# Card_Edge_Board.net
KiCad netlist of a schematic drawn in EAGLE
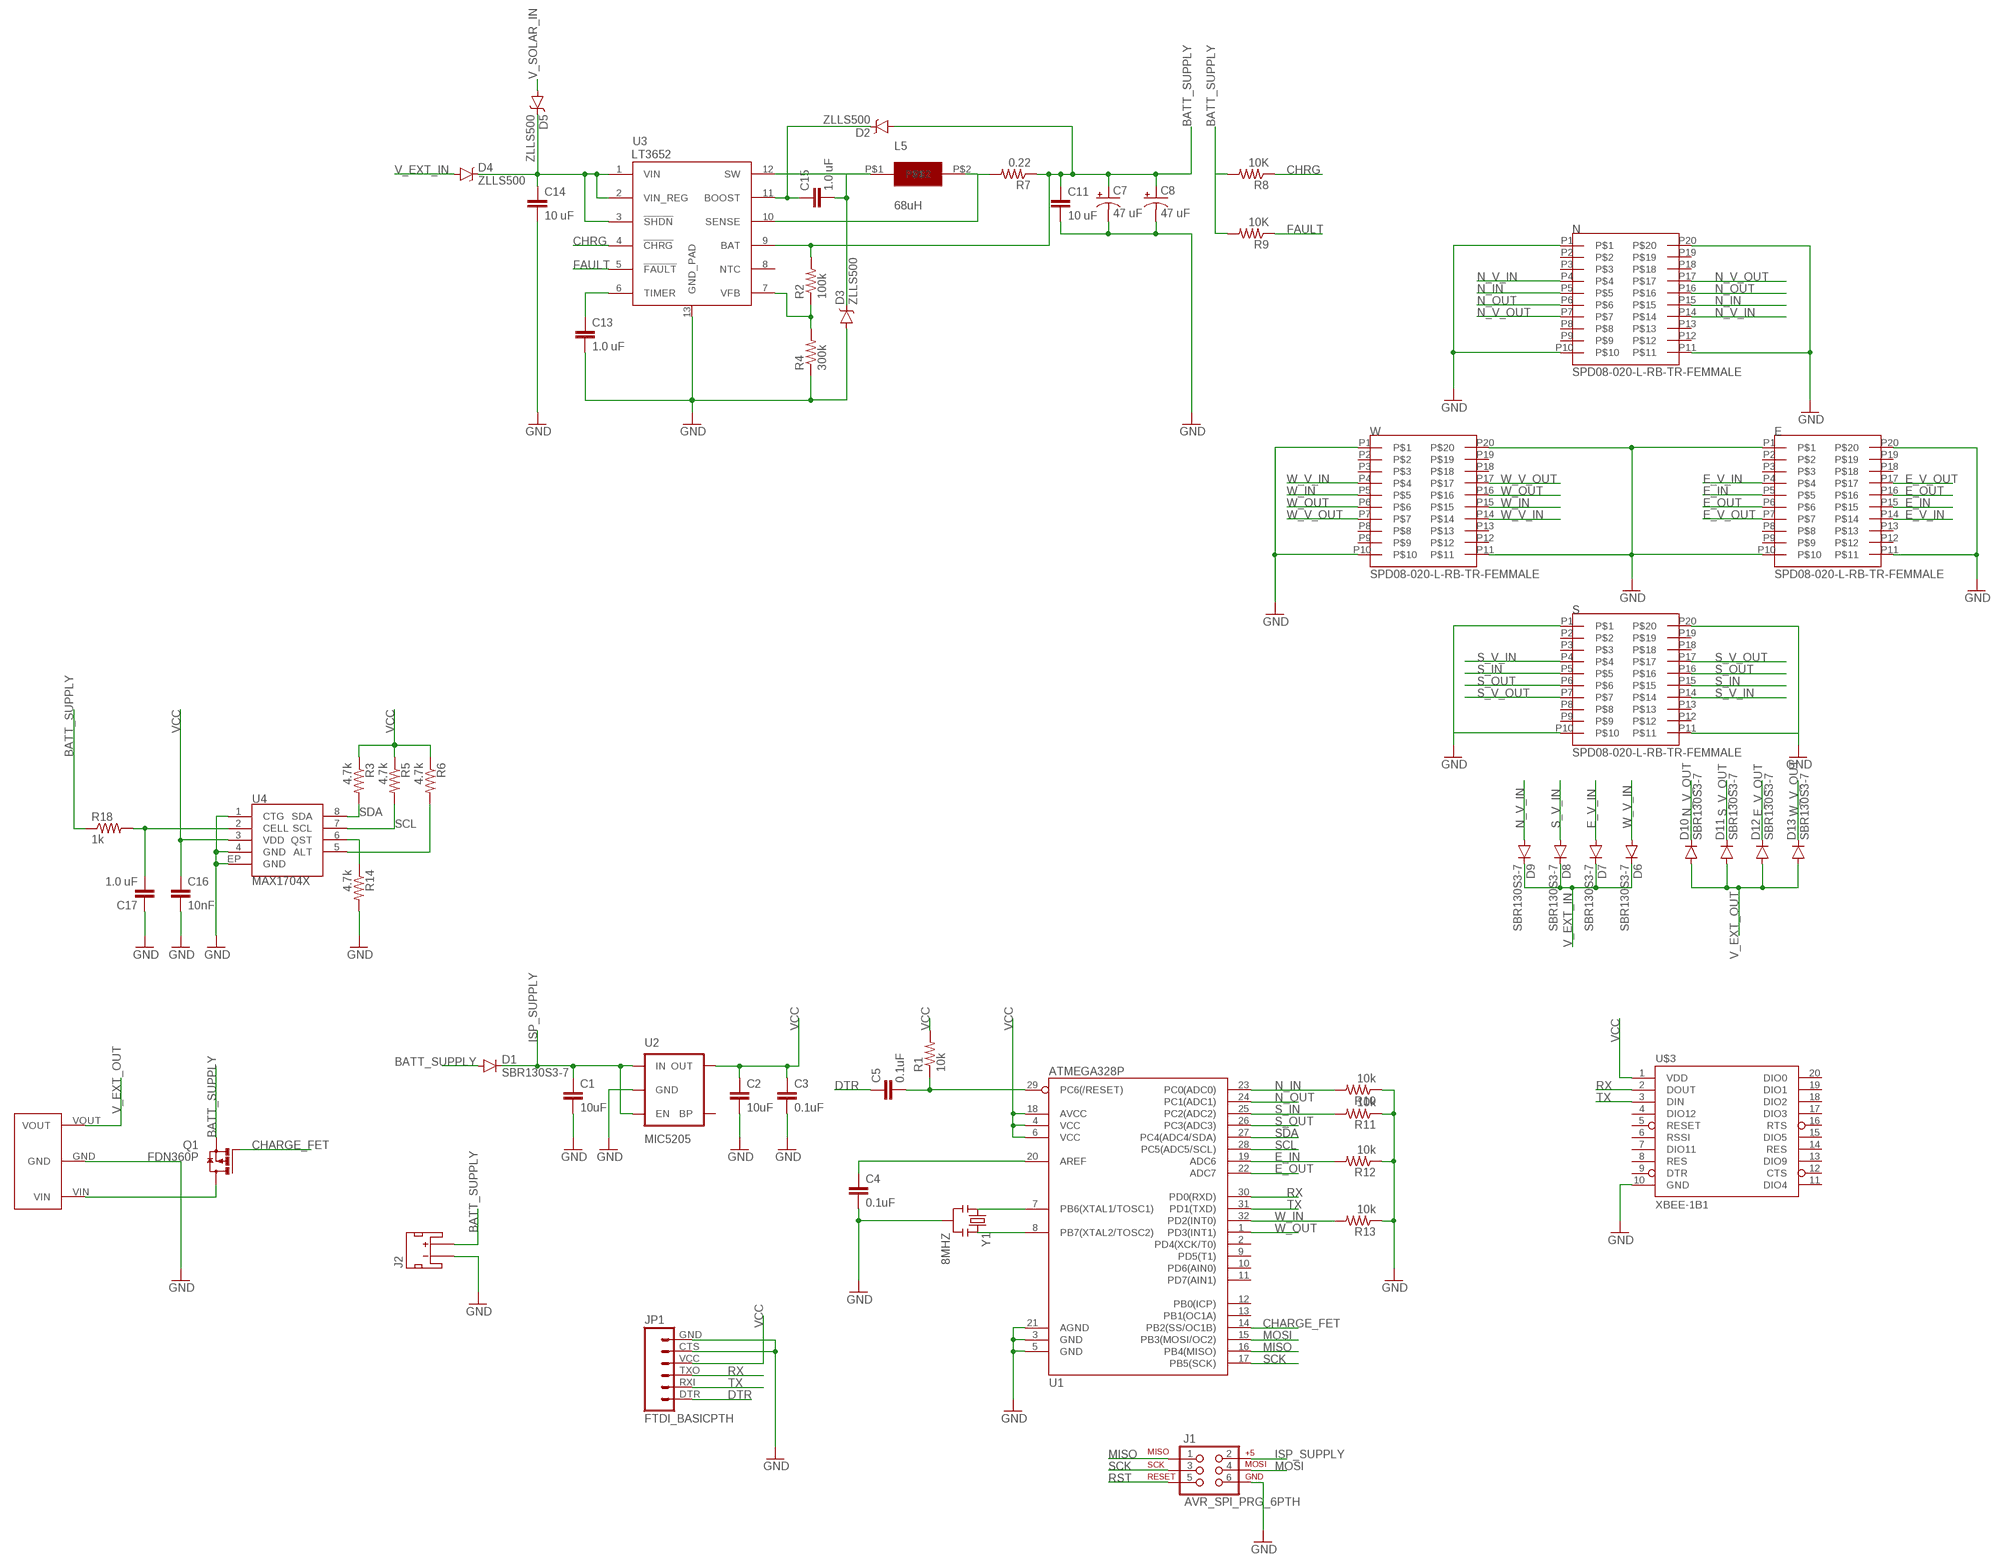
[diagram p0: schematic, sheet 1]

(export (version "E")
  (design (tool "Eeschema 10.0.6"))
  (components
    (comp (ref "C1")
      (value "10uF")
      (footprint "eagle-import:1206")
      (libsource (lib "eagle-import") (part "CAP1206"))
    )
    (comp (ref "C2")
      (value "10uF")
      (footprint "eagle-import:1206")
      (libsource (lib "eagle-import") (part "CAP1206"))
    )
    (comp (ref "C3")
      (value "0.1uF")
      (footprint "eagle-import:1206")
      (libsource (lib "eagle-import") (part "CAP1206"))
    )
    (comp (ref "C4")
      (value "0.1uF")
      (footprint "eagle-import:1206")
      (libsource (lib "eagle-import") (part "CAP1206"))
    )
    (comp (ref "C5")
      (value "0.1uF")
      (footprint "eagle-import:1206")
      (libsource (lib "eagle-import") (part "CAP1206"))
    )
    (comp (ref "C7")
      (value "47 uF")
      (footprint "eagle-import:EIA3216")
      (libsource (lib "eagle-import") (part "CAP_POL1206"))
    )
    (comp (ref "C8")
      (value "47 uF")
      (footprint "eagle-import:EIA3216")
      (libsource (lib "eagle-import") (part "CAP_POL1206"))
    )
    (comp (ref "C11")
      (value "10 uF")
      (footprint "eagle-import:1206")
      (libsource (lib "eagle-import") (part "10UF-6.3V-20%(1206)"))
    )
    (comp (ref "C13")
      (value "1.0 uF")
      (footprint "eagle-import:1206")
      (libsource (lib "eagle-import") (part "10UF-6.3V-20%(1206)"))
    )
    (comp (ref "C14")
      (value "10 uF")
      (footprint "eagle-import:1206")
      (libsource (lib "eagle-import") (part "10UF-6.3V-20%(1206)"))
    )
    (comp (ref "C15")
      (value "1.0 uF")
      (footprint "eagle-import:1206")
      (libsource (lib "eagle-import") (part "10UF-6.3V-20%(1206)"))
    )
    (comp (ref "C16")
      (value "10nF")
      (footprint "eagle-import:1206")
      (libsource (lib "eagle-import") (part "10UF-6.3V-20%(1206)"))
    )
    (comp (ref "C17")
      (value "1.0 uF")
      (footprint "eagle-import:1206")
      (libsource (lib "eagle-import") (part "10UF-6.3V-20%(1206)"))
    )
    (comp (ref "D1")
      (value "SBR130S3-7")
      (footprint "eagle-import:SOD-323")
      (libsource (lib "eagle-import") (part "DIODESOD"))
    )
    (comp (ref "D2")
      (value "ZLLS500")
      (footprint "eagle-import:SOT23")
      (libsource (lib "eagle-import") (part "ZLLS500ZLLS500"))
    )
    (comp (ref "D3")
      (value "ZLLS500")
      (footprint "eagle-import:SOT23")
      (libsource (lib "eagle-import") (part "ZLLS500ZLLS500"))
    )
    (comp (ref "D4")
      (value "ZLLS500")
      (footprint "eagle-import:SOT23")
      (libsource (lib "eagle-import") (part "ZLLS500ZLLS500"))
    )
    (comp (ref "D5")
      (value "ZLLS500")
      (footprint "eagle-import:SOT23")
      (libsource (lib "eagle-import") (part "ZLLS500ZLLS500"))
    )
    (comp (ref "D6")
      (value "SBR130S3-7")
      (footprint "eagle-import:SOD-323")
      (libsource (lib "eagle-import") (part "DIODESOD"))
    )
    (comp (ref "D7")
      (value "SBR130S3-7")
      (footprint "eagle-import:SOD-323")
      (libsource (lib "eagle-import") (part "DIODESOD"))
    )
    (comp (ref "D8")
      (value "SBR130S3-7")
      (footprint "eagle-import:SOD-323")
      (libsource (lib "eagle-import") (part "DIODESOD"))
    )
    (comp (ref "D9")
      (value "SBR130S3-7")
      (footprint "eagle-import:SOD-323")
      (libsource (lib "eagle-import") (part "DIODESOD"))
    )
    (comp (ref "D10")
      (value "SBR130S3-7")
      (footprint "eagle-import:SOD-323")
      (libsource (lib "eagle-import") (part "DIODESOD"))
    )
    (comp (ref "D11")
      (value "SBR130S3-7")
      (footprint "eagle-import:SOD-323")
      (libsource (lib "eagle-import") (part "DIODESOD"))
    )
    (comp (ref "D12")
      (value "SBR130S3-7")
      (footprint "eagle-import:SOD-323")
      (libsource (lib "eagle-import") (part "DIODESOD"))
    )
    (comp (ref "D13")
      (value "SBR130S3-7")
      (footprint "eagle-import:SOD-323")
      (libsource (lib "eagle-import") (part "DIODESOD"))
    )
    (comp (ref "E")
      (value "SPD08-020-L-RB-TR-FEMMALE")
      (footprint "eagle-import:SPD08-020-L-RB-TR-FOOT")
      (libsource (lib "eagle-import") (part "SPD08-020-L-RB-TR-FEMMALE"))
    )
    (comp (ref "J1")
      (value "AVR_SPI_PRG_6PTH")
      (footprint "eagle-import:2X3")
      (libsource (lib "eagle-import") (part "AVR_SPI_PRG_6PTH"))
    )
    (comp (ref "J2")
      (value "JST_2MM_MALE")
      (footprint "eagle-import:JST-2-SMD")
      (libsource (lib "eagle-import") (part "JST_2MM_MALE"))
    )
    (comp (ref "JP1")
      (value "FTDI_BASICPTH")
      (footprint "eagle-import:FTDI_BASIC")
      (libsource (lib "eagle-import") (part "FTDI_BASICPTH"))
    )
    (comp (ref "L5")
      (value "68uH")
      (footprint "eagle-import:MURATA_29L68C")
      (libsource (lib "eagle-import") (part "MURATA_29L683CSMD1"))
    )
    (comp (ref "N")
      (value "SPD08-020-L-RB-TR-FEMMALE")
      (footprint "eagle-import:SPD08-020-L-RB-TR-FOOT")
      (libsource (lib "eagle-import") (part "SPD08-020-L-RB-TR-FEMMALE"))
    )
    (comp (ref "Q1")
      (value "FDN360P")
      (footprint "eagle-import:SUPER-SOT3")
      (libsource (lib "eagle-import") (part "FDN360P"))
    )
    (comp (ref "R1")
      (value "10k")
      (footprint "eagle-import:1206")
      (libsource (lib "eagle-import") (part "RESISTOR1206"))
    )
    (comp (ref "R2")
      (value "100k")
      (footprint "eagle-import:1206")
      (libsource (lib "eagle-import") (part "RESISTOR1206"))
    )
    (comp (ref "R3")
      (value "4.7k")
      (footprint "eagle-import:1206")
      (libsource (lib "eagle-import") (part "RESISTOR1206"))
    )
    (comp (ref "R4")
      (value "300k")
      (footprint "eagle-import:1206")
      (libsource (lib "eagle-import") (part "RESISTOR1206"))
    )
    (comp (ref "R5")
      (value "4.7k")
      (footprint "eagle-import:1206")
      (libsource (lib "eagle-import") (part "RESISTOR1206"))
    )
    (comp (ref "R6")
      (value "4.7k")
      (footprint "eagle-import:1206")
      (libsource (lib "eagle-import") (part "RESISTOR1206"))
    )
    (comp (ref "R7")
      (value "0.22")
      (footprint "eagle-import:1206")
      (libsource (lib "eagle-import") (part "RESISTOR1206"))
    )
    (comp (ref "R8")
      (value "10K")
      (footprint "eagle-import:1206")
      (libsource (lib "eagle-import") (part "RESISTOR1206"))
    )
    (comp (ref "R9")
      (value "10K")
      (footprint "eagle-import:1206")
      (libsource (lib "eagle-import") (part "RESISTOR1206"))
    )
    (comp (ref "R10")
      (value "10k")
      (footprint "eagle-import:1206")
      (libsource (lib "eagle-import") (part "RESISTOR1206"))
    )
    (comp (ref "R11")
      (value "10k")
      (footprint "eagle-import:1206")
      (libsource (lib "eagle-import") (part "RESISTOR1206"))
    )
    (comp (ref "R12")
      (value "10k")
      (footprint "eagle-import:1206")
      (libsource (lib "eagle-import") (part "RESISTOR1206"))
    )
    (comp (ref "R13")
      (value "10k")
      (footprint "eagle-import:1206")
      (libsource (lib "eagle-import") (part "RESISTOR1206"))
    )
    (comp (ref "R14")
      (value "4.7k")
      (footprint "eagle-import:1206")
      (libsource (lib "eagle-import") (part "RESISTOR1206"))
    )
    (comp (ref "R18")
      (value "1k")
      (footprint "eagle-import:1206")
      (libsource (lib "eagle-import") (part "RESISTOR1206"))
    )
    (comp (ref "S")
      (value "SPD08-020-L-RB-TR-FEMMALE")
      (footprint "eagle-import:SPD08-020-L-RB-TR-FOOT")
      (libsource (lib "eagle-import") (part "SPD08-020-L-RB-TR-FEMMALE"))
    )
    (comp (ref "U$1")
      (value "POLOLU791BOOSTPOLOLU")
      (footprint "eagle-import:POLOLU791_BOOST")
      (libsource (lib "eagle-import") (part "POLOLU791BOOSTPOLOLU"))
    )
    (comp (ref "U$3")
      (value "XBEE-1B1")
      (footprint "eagle-import:XBEE-1")
      (libsource (lib "eagle-import") (part "XBEE-1B1"))
    )
    (comp (ref "U1")
      (value "ATMEGA328P")
      (footprint "eagle-import:TQFP32-08")
      (libsource (lib "eagle-import") (part "ATMEGA328_SMT"))
    )
    (comp (ref "U2")
      (value "MIC5205")
      (footprint "eagle-import:SOT23-5")
      (libsource (lib "eagle-import") (part "MIC52053.3V"))
    )
    (comp (ref "U3")
      (value "LT3652")
      (footprint "eagle-import:MSOP-12_GND")
      (libsource (lib "eagle-import") (part "LT3652"))
    )
    (comp (ref "U4")
      (value "MAX1704X")
      (footprint "eagle-import:TDFN-8")
      (libsource (lib "eagle-import") (part "MAX1704X"))
    )
    (comp (ref "W")
      (value "SPD08-020-L-RB-TR-FEMMALE")
      (footprint "eagle-import:SPD08-020-L-RB-TR-FOOT")
      (libsource (lib "eagle-import") (part "SPD08-020-L-RB-TR-FEMMALE"))
    )
    (comp (ref "Y1")
      (value "8MHZ")
      (footprint "eagle-import:RESONATOR-SMD")
      (libsource (lib "eagle-import") (part "RESONATOR8MHZ"))
    )
  )
  (nets
    (net (code "1") (name "/BATT_SUPPLY") (class "Default")
      (node (ref "C11") (pin "1") (pinfunction "1_1") (pintype "passive"))
      (node (ref "C7") (pin "A") (pinfunction "+_A") (pintype "passive"))
      (node (ref "C8") (pin "A") (pinfunction "+_A") (pintype "passive"))
      (node (ref "D1") (pin "A") (pinfunction "A_A") (pintype "passive"))
      (node (ref "D2") (pin "1") (pinfunction "A_1") (pintype "passive"))
      (node (ref "J2") (pin "2") (pinfunction "+_2") (pintype "bidirectional"))
      (node (ref "Q1") (pin "2") (pinfunction "S_2") (pintype "passive"))
      (node (ref "R18") (pin "1") (pinfunction "1_1") (pintype "passive"))
      (node (ref "R2") (pin "2") (pinfunction "2_2") (pintype "passive"))
      (node (ref "R7") (pin "1") (pinfunction "1_1") (pintype "passive"))
      (node (ref "R8") (pin "2") (pinfunction "2_2") (pintype "passive"))
      (node (ref "R9") (pin "2") (pinfunction "2_2") (pintype "passive"))
      (node (ref "U3") (pin "9") (pinfunction "BAT_9") (pintype "bidirectional"))
    )
    (net (code "2") (name "/CHARGE_FET") (class "Default")
      (node (ref "Q1") (pin "1") (pinfunction "G_1") (pintype "passive"))
      (node (ref "U1") (pin "14") (pinfunction "PB2(SS/OC1B)_14") (pintype "bidirectional"))
    )
    (net (code "3") (name "/CHRG") (class "Default")
      (node (ref "R8") (pin "1") (pinfunction "1_1") (pintype "passive"))
      (node (ref "U3") (pin "4") (pinfunction "~{CHRG}_4") (pintype "bidirectional"))
    )
    (net (code "4") (name "/DTR") (class "Default")
      (node (ref "C5") (pin "1") (pinfunction "1_1") (pintype "passive"))
      (node (ref "JP1") (pin "DTR") (pinfunction "1_DTR") (pintype "passive"))
    )
    (net (code "5") (name "/E_IN") (class "Default")
      (node (ref "E") (pin "P15") (pinfunction "P$15_P15") (pintype "bidirectional"))
      (node (ref "E") (pin "P5") (pinfunction "P$5_P5") (pintype "bidirectional"))
      (node (ref "R12") (pin "2") (pinfunction "2_2") (pintype "passive"))
      (node (ref "U1") (pin "19") (pinfunction "ADC6_19") (pintype "bidirectional"))
    )
    (net (code "6") (name "/E_OUT") (class "Default")
      (node (ref "E") (pin "P16") (pinfunction "P$16_P16") (pintype "bidirectional"))
      (node (ref "E") (pin "P6") (pinfunction "P$6_P6") (pintype "bidirectional"))
      (node (ref "U1") (pin "22") (pinfunction "ADC7_22") (pintype "bidirectional"))
    )
    (net (code "7") (name "/E_V_IN") (class "Default")
      (node (ref "D7") (pin "A") (pinfunction "A_A") (pintype "passive"))
      (node (ref "E") (pin "P14") (pinfunction "P$14_P14") (pintype "bidirectional"))
      (node (ref "E") (pin "P4") (pinfunction "P$4_P4") (pintype "bidirectional"))
    )
    (net (code "8") (name "/E_V_OUT") (class "Default")
      (node (ref "D12") (pin "C") (pinfunction "C_C") (pintype "passive"))
      (node (ref "E") (pin "P17") (pinfunction "P$17_P17") (pintype "bidirectional"))
      (node (ref "E") (pin "P7") (pinfunction "P$7_P7") (pintype "bidirectional"))
    )
    (net (code "9") (name "/FAULT") (class "Default")
      (node (ref "R9") (pin "1") (pinfunction "1_1") (pintype "passive"))
      (node (ref "U3") (pin "5") (pinfunction "~{FAULT}_5") (pintype "bidirectional"))
    )
    (net (code "10") (name "/ISP_SUPPLY") (class "Default")
      (node (ref "C1") (pin "1") (pinfunction "1_1") (pintype "passive"))
      (node (ref "D1") (pin "C") (pinfunction "C_C") (pintype "passive"))
      (node (ref "J1") (pin "2") (pinfunction "2_2") (pintype "passive"))
      (node (ref "U2") (pin "1") (pinfunction "IN_1") (pintype "input"))
      (node (ref "U2") (pin "3") (pinfunction "EN_3") (pintype "input"))
    )
    (net (code "11") (name "/MISO") (class "Default")
      (node (ref "J1") (pin "1") (pinfunction "1_1") (pintype "passive"))
      (node (ref "U1") (pin "16") (pinfunction "PB4(MISO)_16") (pintype "bidirectional"))
    )
    (net (code "12") (name "/MOSI") (class "Default")
      (node (ref "J1") (pin "4") (pinfunction "4_4") (pintype "passive"))
      (node (ref "U1") (pin "15") (pinfunction "PB3(MOSI/OC2)_15") (pintype "bidirectional"))
    )
    (net (code "13") (name "/N_IN") (class "Default")
      (node (ref "N") (pin "P15") (pinfunction "P$15_P15") (pintype "bidirectional"))
      (node (ref "N") (pin "P5") (pinfunction "P$5_P5") (pintype "bidirectional"))
      (node (ref "R10") (pin "2") (pinfunction "2_2") (pintype "passive"))
      (node (ref "U1") (pin "23") (pinfunction "PC0(ADC0)_23") (pintype "bidirectional"))
    )
    (net (code "14") (name "/N_OUT") (class "Default")
      (node (ref "N") (pin "P16") (pinfunction "P$16_P16") (pintype "bidirectional"))
      (node (ref "N") (pin "P6") (pinfunction "P$6_P6") (pintype "bidirectional"))
      (node (ref "U1") (pin "24") (pinfunction "PC1(ADC1)_24") (pintype "bidirectional"))
    )
    (net (code "15") (name "/N_V_IN") (class "Default")
      (node (ref "D9") (pin "A") (pinfunction "A_A") (pintype "passive"))
      (node (ref "N") (pin "P14") (pinfunction "P$14_P14") (pintype "bidirectional"))
      (node (ref "N") (pin "P4") (pinfunction "P$4_P4") (pintype "bidirectional"))
    )
    (net (code "16") (name "/N_V_OUT") (class "Default")
      (node (ref "D10") (pin "C") (pinfunction "C_C") (pintype "passive"))
      (node (ref "N") (pin "P17") (pinfunction "P$17_P17") (pintype "bidirectional"))
      (node (ref "N") (pin "P7") (pinfunction "P$7_P7") (pintype "bidirectional"))
    )
    (net (code "17") (name "/RST") (class "Default")
      (node (ref "C5") (pin "2") (pinfunction "2_2") (pintype "passive"))
      (node (ref "J1") (pin "5") (pinfunction "5_5") (pintype "passive"))
      (node (ref "R1") (pin "1") (pinfunction "1_1") (pintype "passive"))
      (node (ref "U1") (pin "29") (pinfunction "PC6(/RESET)_29") (pintype "bidirectional"))
    )
    (net (code "18") (name "/RX") (class "Default")
      (node (ref "JP1") (pin "TXO") (pinfunction "3_TXO") (pintype "passive"))
      (node (ref "U$3") (pin "2") (pinfunction "DOUT_2") (pintype "output"))
      (node (ref "U1") (pin "30") (pinfunction "PD0(RXD)_30") (pintype "bidirectional"))
    )
    (net (code "19") (name "/SCK") (class "Default")
      (node (ref "J1") (pin "3") (pinfunction "3_3") (pintype "passive"))
      (node (ref "U1") (pin "17") (pinfunction "PB5(SCK)_17") (pintype "bidirectional"))
    )
    (net (code "20") (name "/SCL") (class "Default")
      (node (ref "R5") (pin "2") (pinfunction "2_2") (pintype "passive"))
      (node (ref "U1") (pin "28") (pinfunction "PC5(ADC5/SCL)_28") (pintype "bidirectional"))
      (node (ref "U4") (pin "7") (pinfunction "SCL_7") (pintype "bidirectional"))
    )
    (net (code "21") (name "/SDA") (class "Default")
      (node (ref "R3") (pin "2") (pinfunction "2_2") (pintype "passive"))
      (node (ref "U1") (pin "27") (pinfunction "PC4(ADC4/SDA)_27") (pintype "bidirectional"))
      (node (ref "U4") (pin "8") (pinfunction "SDA_8") (pintype "bidirectional"))
    )
    (net (code "22") (name "/S_IN") (class "Default")
      (node (ref "R11") (pin "2") (pinfunction "2_2") (pintype "passive"))
      (node (ref "S") (pin "P15") (pinfunction "P$15_P15") (pintype "bidirectional"))
      (node (ref "S") (pin "P5") (pinfunction "P$5_P5") (pintype "bidirectional"))
      (node (ref "U1") (pin "25") (pinfunction "PC2(ADC2)_25") (pintype "bidirectional"))
    )
    (net (code "23") (name "/S_OUT") (class "Default")
      (node (ref "S") (pin "P16") (pinfunction "P$16_P16") (pintype "bidirectional"))
      (node (ref "S") (pin "P6") (pinfunction "P$6_P6") (pintype "bidirectional"))
      (node (ref "U1") (pin "26") (pinfunction "PC3(ADC3)_26") (pintype "bidirectional"))
    )
    (net (code "24") (name "/S_V_IN") (class "Default")
      (node (ref "D8") (pin "A") (pinfunction "A_A") (pintype "passive"))
      (node (ref "S") (pin "P14") (pinfunction "P$14_P14") (pintype "bidirectional"))
      (node (ref "S") (pin "P4") (pinfunction "P$4_P4") (pintype "bidirectional"))
    )
    (net (code "25") (name "/S_V_OUT") (class "Default")
      (node (ref "D11") (pin "C") (pinfunction "C_C") (pintype "passive"))
      (node (ref "S") (pin "P17") (pinfunction "P$17_P17") (pintype "bidirectional"))
      (node (ref "S") (pin "P7") (pinfunction "P$7_P7") (pintype "bidirectional"))
    )
    (net (code "26") (name "/TX") (class "Default")
      (node (ref "JP1") (pin "RXI") (pinfunction "2_RXI") (pintype "passive"))
      (node (ref "U$3") (pin "3") (pinfunction "DIN_3") (pintype "input"))
      (node (ref "U1") (pin "31") (pinfunction "PD1(TXD)_31") (pintype "bidirectional"))
    )
    (net (code "27") (name "/VCC") (class "Default")
      (node (ref "C16") (pin "1") (pinfunction "1_1") (pintype "passive"))
      (node (ref "C2") (pin "1") (pinfunction "1_1") (pintype "passive"))
      (node (ref "C3") (pin "1") (pinfunction "1_1") (pintype "passive"))
      (node (ref "JP1") (pin "VCC") (pinfunction "4_VCC") (pintype "passive"))
      (node (ref "R1") (pin "2") (pinfunction "2_2") (pintype "passive"))
      (node (ref "R3") (pin "1") (pinfunction "1_1") (pintype "passive"))
      (node (ref "R5") (pin "1") (pinfunction "1_1") (pintype "passive"))
      (node (ref "R6") (pin "1") (pinfunction "1_1") (pintype "passive"))
      (node (ref "U$3") (pin "1") (pinfunction "VDD_1") (pintype "power_in"))
      (node (ref "U1") (pin "18") (pinfunction "AVCC_18") (pintype "bidirectional"))
      (node (ref "U1") (pin "4") (pinfunction "VCC_4") (pintype "bidirectional"))
      (node (ref "U1") (pin "6") (pinfunction "VCC_6") (pintype "bidirectional"))
      (node (ref "U2") (pin "5") (pinfunction "OUT_5") (pintype "passive"))
      (node (ref "U4") (pin "3") (pinfunction "VDD_3") (pintype "bidirectional"))
    )
    (net (code "28") (name "/V_EXT_IN") (class "Default")
      (node (ref "D4") (pin "1") (pinfunction "A_1") (pintype "passive"))
      (node (ref "D6") (pin "C") (pinfunction "C_C") (pintype "passive"))
      (node (ref "D7") (pin "C") (pinfunction "C_C") (pintype "passive"))
      (node (ref "D8") (pin "C") (pinfunction "C_C") (pintype "passive"))
      (node (ref "D9") (pin "C") (pinfunction "C_C") (pintype "passive"))
    )
    (net (code "29") (name "/V_EXT_OUT") (class "Default")
      (node (ref "D10") (pin "A") (pinfunction "A_A") (pintype "passive"))
      (node (ref "D11") (pin "A") (pinfunction "A_A") (pintype "passive"))
      (node (ref "D12") (pin "A") (pinfunction "A_A") (pintype "passive"))
      (node (ref "D13") (pin "A") (pinfunction "A_A") (pintype "passive"))
      (node (ref "U$1") (pin "VOUT") (pinfunction "VOUT_VOUT") (pintype "bidirectional"))
    )
    (net (code "30") (name "/V_SOLAR_IN") (class "Default")
      (node (ref "D5") (pin "1") (pinfunction "A_1") (pintype "passive"))
    )
    (net (code "31") (name "/W_IN") (class "Default")
      (node (ref "R13") (pin "2") (pinfunction "2_2") (pintype "passive"))
      (node (ref "U1") (pin "32") (pinfunction "PD2(INT0)_32") (pintype "bidirectional"))
      (node (ref "W") (pin "P15") (pinfunction "P$15_P15") (pintype "bidirectional"))
      (node (ref "W") (pin "P5") (pinfunction "P$5_P5") (pintype "bidirectional"))
    )
    (net (code "32") (name "/W_OUT") (class "Default")
      (node (ref "U1") (pin "1") (pinfunction "PD3(INT1)_1") (pintype "bidirectional"))
      (node (ref "W") (pin "P16") (pinfunction "P$16_P16") (pintype "bidirectional"))
      (node (ref "W") (pin "P6") (pinfunction "P$6_P6") (pintype "bidirectional"))
    )
    (net (code "33") (name "/W_V_IN") (class "Default")
      (node (ref "D6") (pin "A") (pinfunction "A_A") (pintype "passive"))
      (node (ref "W") (pin "P14") (pinfunction "P$14_P14") (pintype "bidirectional"))
      (node (ref "W") (pin "P4") (pinfunction "P$4_P4") (pintype "bidirectional"))
    )
    (net (code "34") (name "/W_V_OUT") (class "Default")
      (node (ref "D13") (pin "C") (pinfunction "C_C") (pintype "passive"))
      (node (ref "W") (pin "P17") (pinfunction "P$17_P17") (pintype "bidirectional"))
      (node (ref "W") (pin "P7") (pinfunction "P$7_P7") (pintype "bidirectional"))
    )
    (net (code "35") (name "GND") (class "Default")
      (node (ref "C1") (pin "2") (pinfunction "2_2") (pintype "passive"))
      (node (ref "C11") (pin "2") (pinfunction "2_2") (pintype "passive"))
      (node (ref "C13") (pin "2") (pinfunction "2_2") (pintype "passive"))
      (node (ref "C14") (pin "2") (pinfunction "2_2") (pintype "passive"))
      (node (ref "C16") (pin "2") (pinfunction "2_2") (pintype "passive"))
      (node (ref "C17") (pin "1") (pinfunction "1_1") (pintype "passive"))
      (node (ref "C2") (pin "2") (pinfunction "2_2") (pintype "passive"))
      (node (ref "C3") (pin "2") (pinfunction "2_2") (pintype "passive"))
      (node (ref "C4") (pin "2") (pinfunction "2_2") (pintype "passive"))
      (node (ref "C7") (pin "C") (pinfunction "-_C") (pintype "passive"))
      (node (ref "C8") (pin "C") (pinfunction "-_C") (pintype "passive"))
      (node (ref "D3") (pin "1") (pinfunction "A_1") (pintype "passive"))
      (node (ref "E") (pin "P1") (pinfunction "P$1_P1") (pintype "bidirectional"))
      (node (ref "E") (pin "P10") (pinfunction "P$10_P10") (pintype "bidirectional"))
      (node (ref "E") (pin "P11") (pinfunction "P$11_P11") (pintype "bidirectional"))
      (node (ref "E") (pin "P20") (pinfunction "P$20_P20") (pintype "bidirectional"))
      (node (ref "J1") (pin "6") (pinfunction "6_6") (pintype "passive"))
      (node (ref "J2") (pin "1") (pinfunction "-_1") (pintype "bidirectional"))
      (node (ref "JP1") (pin "CTS") (pinfunction "5_CTS") (pintype "passive"))
      (node (ref "JP1") (pin "GND") (pinfunction "6_GND") (pintype "passive"))
      (node (ref "N") (pin "P1") (pinfunction "P$1_P1") (pintype "bidirectional"))
      (node (ref "N") (pin "P10") (pinfunction "P$10_P10") (pintype "bidirectional"))
      (node (ref "N") (pin "P11") (pinfunction "P$11_P11") (pintype "bidirectional"))
      (node (ref "N") (pin "P20") (pinfunction "P$20_P20") (pintype "bidirectional"))
      (node (ref "R10") (pin "1") (pinfunction "1_1") (pintype "passive"))
      (node (ref "R11") (pin "1") (pinfunction "1_1") (pintype "passive"))
      (node (ref "R12") (pin "1") (pinfunction "1_1") (pintype "passive"))
      (node (ref "R13") (pin "1") (pinfunction "1_1") (pintype "passive"))
      (node (ref "R14") (pin "2") (pinfunction "2_2") (pintype "passive"))
      (node (ref "R4") (pin "1") (pinfunction "1_1") (pintype "passive"))
      (node (ref "S") (pin "P1") (pinfunction "P$1_P1") (pintype "bidirectional"))
      (node (ref "S") (pin "P10") (pinfunction "P$10_P10") (pintype "bidirectional"))
      (node (ref "S") (pin "P11") (pinfunction "P$11_P11") (pintype "bidirectional"))
      (node (ref "S") (pin "P20") (pinfunction "P$20_P20") (pintype "bidirectional"))
      (node (ref "U$1") (pin "GND") (pinfunction "GND_GND") (pintype "bidirectional"))
      (node (ref "U$3") (pin "10") (pinfunction "GND_10") (pintype "power_in"))
      (node (ref "U1") (pin "21") (pinfunction "AGND_21") (pintype "bidirectional"))
      (node (ref "U1") (pin "3") (pinfunction "GND_3") (pintype "bidirectional"))
      (node (ref "U1") (pin "5") (pinfunction "GND_5") (pintype "bidirectional"))
      (node (ref "U2") (pin "2") (pinfunction "GND_2") (pintype "input"))
      (node (ref "U3") (pin "13") (pinfunction "GND_PAD_13") (pintype "bidirectional"))
      (node (ref "U4") (pin "1") (pinfunction "CTG_1") (pintype "bidirectional"))
      (node (ref "U4") (pin "4") (pinfunction "GND_4") (pintype "bidirectional"))
      (node (ref "U4") (pin "EP") (pinfunction "GND_EP") (pintype "bidirectional"))
      (node (ref "W") (pin "P1") (pinfunction "P$1_P1") (pintype "bidirectional"))
      (node (ref "W") (pin "P10") (pinfunction "P$10_P10") (pintype "bidirectional"))
      (node (ref "W") (pin "P11") (pinfunction "P$11_P11") (pintype "bidirectional"))
      (node (ref "W") (pin "P20") (pinfunction "P$20_P20") (pintype "bidirectional"))
      (node (ref "Y1") (pin "2") (pinfunction "2_2") (pintype "passive"))
    )
    (net (code "36") (name "Net-(D2-C)") (class "Default")
      (node (ref "C15") (pin "1") (pinfunction "1_1") (pintype "passive"))
      (node (ref "D2") (pin "3") (pinfunction "C_3") (pintype "passive"))
      (node (ref "U3") (pin "11") (pinfunction "BOOST_11") (pintype "bidirectional"))
    )
    (net (code "37") (name "Net-(D3-C)") (class "Default")
      (node (ref "C15") (pin "2") (pinfunction "2_2") (pintype "passive"))
      (node (ref "D3") (pin "3") (pinfunction "C_3") (pintype "passive"))
      (node (ref "L5") (pin "P$1") (pinfunction "P$1_P$1") (pintype "bidirectional"))
      (node (ref "U3") (pin "12") (pinfunction "SW_12") (pintype "bidirectional"))
    )
    (net (code "38") (name "Net-(D4-C)") (class "Default")
      (node (ref "C14") (pin "1") (pinfunction "1_1") (pintype "passive"))
      (node (ref "D4") (pin "3") (pinfunction "C_3") (pintype "passive"))
      (node (ref "D5") (pin "3") (pinfunction "C_3") (pintype "passive"))
      (node (ref "U3") (pin "1") (pinfunction "VIN_1") (pintype "bidirectional"))
      (node (ref "U3") (pin "2") (pinfunction "VIN_REG_2") (pintype "bidirectional"))
      (node (ref "U3") (pin "3") (pinfunction "~{SHDN}_3") (pintype "bidirectional"))
    )
    (net (code "39") (name "Net-(Q1-D)") (class "Default")
      (node (ref "Q1") (pin "3") (pinfunction "D_3") (pintype "passive"))
      (node (ref "U$1") (pin "VIN") (pinfunction "VIN_VIN") (pintype "bidirectional"))
    )
    (net (code "40") (name "Net-(U1-AREF)") (class "Default")
      (node (ref "C4") (pin "1") (pinfunction "1_1") (pintype "passive"))
      (node (ref "U1") (pin "20") (pinfunction "AREF_20") (pintype "bidirectional"))
    )
    (net (code "41") (name "Net-(U1-PB6(XTAL1{slash}TOSC1))") (class "Default")
      (node (ref "U1") (pin "7") (pinfunction "PB6(XTAL1/TOSC1)_7") (pintype "bidirectional"))
      (node (ref "Y1") (pin "1") (pinfunction "1_1") (pintype "passive"))
    )
    (net (code "42") (name "Net-(U1-PB7(XTAL2{slash}TOSC2))") (class "Default")
      (node (ref "U1") (pin "8") (pinfunction "PB7(XTAL2/TOSC2)_8") (pintype "bidirectional"))
      (node (ref "Y1") (pin "3") (pinfunction "3_3") (pintype "passive"))
    )
    (net (code "43") (name "Net-(U3-SENSE)") (class "Default")
      (node (ref "L5") (pin "P$2") (pinfunction "P$2_P$2") (pintype "bidirectional"))
      (node (ref "R7") (pin "2") (pinfunction "2_2") (pintype "passive"))
      (node (ref "U3") (pin "10") (pinfunction "SENSE_10") (pintype "bidirectional"))
    )
    (net (code "44") (name "Net-(U3-TIMER)") (class "Default")
      (node (ref "C13") (pin "1") (pinfunction "1_1") (pintype "passive"))
      (node (ref "U3") (pin "6") (pinfunction "TIMER_6") (pintype "bidirectional"))
    )
    (net (code "45") (name "Net-(U3-VFB)") (class "Default")
      (node (ref "R2") (pin "1") (pinfunction "1_1") (pintype "passive"))
      (node (ref "R4") (pin "2") (pinfunction "2_2") (pintype "passive"))
      (node (ref "U3") (pin "7") (pinfunction "VFB_7") (pintype "bidirectional"))
    )
    (net (code "46") (name "Net-(U4-ALT)") (class "Default")
      (node (ref "R6") (pin "2") (pinfunction "2_2") (pintype "passive"))
      (node (ref "U4") (pin "5") (pinfunction "ALT_5") (pintype "bidirectional"))
    )
    (net (code "47") (name "Net-(U4-CELL)") (class "Default")
      (node (ref "C17") (pin "2") (pinfunction "2_2") (pintype "passive"))
      (node (ref "R18") (pin "2") (pinfunction "2_2") (pintype "passive"))
      (node (ref "U4") (pin "2") (pinfunction "CELL_2") (pintype "bidirectional"))
    )
    (net (code "48") (name "Net-(U4-QST)") (class "Default")
      (node (ref "R14") (pin "1") (pinfunction "1_1") (pintype "passive"))
      (node (ref "U4") (pin "6") (pinfunction "QST_6") (pintype "bidirectional"))
    )
    (net (code "49") (name "unconnected-(E-P$2-PadP2)") (class "Default")
      (node (ref "E") (pin "P2") (pinfunction "P$2_P2") (pintype "bidirectional"))
    )
    (net (code "50") (name "unconnected-(E-P$3-PadP3)") (class "Default")
      (node (ref "E") (pin "P3") (pinfunction "P$3_P3") (pintype "bidirectional"))
    )
    (net (code "51") (name "unconnected-(E-P$8-PadP8)") (class "Default")
      (node (ref "E") (pin "P8") (pinfunction "P$8_P8") (pintype "bidirectional"))
    )
    (net (code "52") (name "unconnected-(E-P$9-PadP9)") (class "Default")
      (node (ref "E") (pin "P9") (pinfunction "P$9_P9") (pintype "bidirectional"))
    )
    (net (code "53") (name "unconnected-(E-P$12-PadP12)") (class "Default")
      (node (ref "E") (pin "P12") (pinfunction "P$12_P12") (pintype "bidirectional"))
    )
    (net (code "54") (name "unconnected-(E-P$13-PadP13)") (class "Default")
      (node (ref "E") (pin "P13") (pinfunction "P$13_P13") (pintype "bidirectional"))
    )
    (net (code "55") (name "unconnected-(E-P$18-PadP18)") (class "Default")
      (node (ref "E") (pin "P18") (pinfunction "P$18_P18") (pintype "bidirectional"))
    )
    (net (code "56") (name "unconnected-(E-P$19-PadP19)") (class "Default")
      (node (ref "E") (pin "P19") (pinfunction "P$19_P19") (pintype "bidirectional"))
    )
    (net (code "57") (name "unconnected-(J2-PAD1-PadNC1)") (class "Default")
      (node (ref "J2") (pin "NC1") (pinfunction "PAD1_NC1") (pintype "bidirectional"))
    )
    (net (code "58") (name "unconnected-(J2-PAD2-PadNC2)") (class "Default")
      (node (ref "J2") (pin "NC2") (pinfunction "PAD2_NC2") (pintype "bidirectional"))
    )
    (net (code "59") (name "unconnected-(N-P$2-PadP2)") (class "Default")
      (node (ref "N") (pin "P2") (pinfunction "P$2_P2") (pintype "bidirectional"))
    )
    (net (code "60") (name "unconnected-(N-P$3-PadP3)") (class "Default")
      (node (ref "N") (pin "P3") (pinfunction "P$3_P3") (pintype "bidirectional"))
    )
    (net (code "61") (name "unconnected-(N-P$8-PadP8)") (class "Default")
      (node (ref "N") (pin "P8") (pinfunction "P$8_P8") (pintype "bidirectional"))
    )
    (net (code "62") (name "unconnected-(N-P$9-PadP9)") (class "Default")
      (node (ref "N") (pin "P9") (pinfunction "P$9_P9") (pintype "bidirectional"))
    )
    (net (code "63") (name "unconnected-(N-P$12-PadP12)") (class "Default")
      (node (ref "N") (pin "P12") (pinfunction "P$12_P12") (pintype "bidirectional"))
    )
    (net (code "64") (name "unconnected-(N-P$13-PadP13)") (class "Default")
      (node (ref "N") (pin "P13") (pinfunction "P$13_P13") (pintype "bidirectional"))
    )
    (net (code "65") (name "unconnected-(N-P$18-PadP18)") (class "Default")
      (node (ref "N") (pin "P18") (pinfunction "P$18_P18") (pintype "bidirectional"))
    )
    (net (code "66") (name "unconnected-(N-P$19-PadP19)") (class "Default")
      (node (ref "N") (pin "P19") (pinfunction "P$19_P19") (pintype "bidirectional"))
    )
    (net (code "67") (name "unconnected-(S-P$2-PadP2)") (class "Default")
      (node (ref "S") (pin "P2") (pinfunction "P$2_P2") (pintype "bidirectional"))
    )
    (net (code "68") (name "unconnected-(S-P$3-PadP3)") (class "Default")
      (node (ref "S") (pin "P3") (pinfunction "P$3_P3") (pintype "bidirectional"))
    )
    (net (code "69") (name "unconnected-(S-P$8-PadP8)") (class "Default")
      (node (ref "S") (pin "P8") (pinfunction "P$8_P8") (pintype "bidirectional"))
    )
    (net (code "70") (name "unconnected-(S-P$9-PadP9)") (class "Default")
      (node (ref "S") (pin "P9") (pinfunction "P$9_P9") (pintype "bidirectional"))
    )
    (net (code "71") (name "unconnected-(S-P$12-PadP12)") (class "Default")
      (node (ref "S") (pin "P12") (pinfunction "P$12_P12") (pintype "bidirectional"))
    )
    (net (code "72") (name "unconnected-(S-P$13-PadP13)") (class "Default")
      (node (ref "S") (pin "P13") (pinfunction "P$13_P13") (pintype "bidirectional"))
    )
    (net (code "73") (name "unconnected-(S-P$18-PadP18)") (class "Default")
      (node (ref "S") (pin "P18") (pinfunction "P$18_P18") (pintype "bidirectional"))
    )
    (net (code "74") (name "unconnected-(S-P$19-PadP19)") (class "Default")
      (node (ref "S") (pin "P19") (pinfunction "P$19_P19") (pintype "bidirectional"))
    )
    (net (code "75") (name "unconnected-(U$3-CTS-Pad12)") (class "Default")
      (node (ref "U$3") (pin "12") (pinfunction "CTS_12") (pintype "output"))
    )
    (net (code "76") (name "unconnected-(U$3-DIO0-Pad20)") (class "Default")
      (node (ref "U$3") (pin "20") (pinfunction "DIO0_20") (pintype "bidirectional"))
    )
    (net (code "77") (name "unconnected-(U$3-DIO1-Pad19)") (class "Default")
      (node (ref "U$3") (pin "19") (pinfunction "DIO1_19") (pintype "bidirectional"))
    )
    (net (code "78") (name "unconnected-(U$3-DIO2-Pad18)") (class "Default")
      (node (ref "U$3") (pin "18") (pinfunction "DIO2_18") (pintype "bidirectional"))
    )
    (net (code "79") (name "unconnected-(U$3-DIO3-Pad17)") (class "Default")
      (node (ref "U$3") (pin "17") (pinfunction "DIO3_17") (pintype "bidirectional"))
    )
    (net (code "80") (name "unconnected-(U$3-DIO4-Pad11)") (class "Default")
      (node (ref "U$3") (pin "11") (pinfunction "DIO4_11") (pintype "bidirectional"))
    )
    (net (code "81") (name "unconnected-(U$3-DIO5-Pad15)") (class "Default")
      (node (ref "U$3") (pin "15") (pinfunction "DIO5_15") (pintype "bidirectional"))
    )
    (net (code "82") (name "unconnected-(U$3-DIO9-Pad13)") (class "Default")
      (node (ref "U$3") (pin "13") (pinfunction "DIO9_13") (pintype "bidirectional"))
    )
    (net (code "83") (name "unconnected-(U$3-DIO11-Pad7)") (class "Default")
      (node (ref "U$3") (pin "7") (pinfunction "DIO11_7") (pintype "bidirectional"))
    )
    (net (code "84") (name "unconnected-(U$3-DIO12-Pad4)") (class "Default")
      (node (ref "U$3") (pin "4") (pinfunction "DIO12_4") (pintype "bidirectional"))
    )
    (net (code "85") (name "unconnected-(U$3-DTR-Pad9)") (class "Default")
      (node (ref "U$3") (pin "9") (pinfunction "DTR_9") (pintype "bidirectional"))
    )
    (net (code "86") (name "unconnected-(U$3-RES-Pad8)") (class "Default")
      (node (ref "U$3") (pin "8") (pinfunction "RES_8") (pintype "bidirectional"))
    )
    (net (code "87") (name "unconnected-(U$3-RES-Pad14)") (class "Default")
      (node (ref "U$3") (pin "14") (pinfunction "RES_14") (pintype "bidirectional"))
    )
    (net (code "88") (name "unconnected-(U$3-RESET-Pad5)") (class "Default")
      (node (ref "U$3") (pin "5") (pinfunction "RESET_5") (pintype "input"))
    )
    (net (code "89") (name "unconnected-(U$3-RSSI-Pad6)") (class "Default")
      (node (ref "U$3") (pin "6") (pinfunction "RSSI_6") (pintype "bidirectional"))
    )
    (net (code "90") (name "unconnected-(U$3-RTS-Pad16)") (class "Default")
      (node (ref "U$3") (pin "16") (pinfunction "RTS_16") (pintype "input"))
    )
    (net (code "91") (name "unconnected-(U1-PB0(ICP)-Pad12)") (class "Default")
      (node (ref "U1") (pin "12") (pinfunction "PB0(ICP)_12") (pintype "bidirectional"))
    )
    (net (code "92") (name "unconnected-(U1-PB1(OC1A)-Pad13)") (class "Default")
      (node (ref "U1") (pin "13") (pinfunction "PB1(OC1A)_13") (pintype "bidirectional"))
    )
    (net (code "93") (name "unconnected-(U1-PD4(XCK{slash}T0)-Pad2)") (class "Default")
      (node (ref "U1") (pin "2") (pinfunction "PD4(XCK/T0)_2") (pintype "bidirectional"))
    )
    (net (code "94") (name "unconnected-(U1-PD5(T1)-Pad9)") (class "Default")
      (node (ref "U1") (pin "9") (pinfunction "PD5(T1)_9") (pintype "bidirectional"))
    )
    (net (code "95") (name "unconnected-(U1-PD6(AIN0)-Pad10)") (class "Default")
      (node (ref "U1") (pin "10") (pinfunction "PD6(AIN0)_10") (pintype "bidirectional"))
    )
    (net (code "96") (name "unconnected-(U1-PD7(AIN1)-Pad11)") (class "Default")
      (node (ref "U1") (pin "11") (pinfunction "PD7(AIN1)_11") (pintype "bidirectional"))
    )
    (net (code "97") (name "unconnected-(U2-BP-Pad4)") (class "Default")
      (node (ref "U2") (pin "4") (pinfunction "BP_4") (pintype "input"))
    )
    (net (code "98") (name "unconnected-(U3-NTC-Pad8)") (class "Default")
      (node (ref "U3") (pin "8") (pinfunction "NTC_8") (pintype "bidirectional"))
    )
    (net (code "99") (name "unconnected-(W-P$2-PadP2)") (class "Default")
      (node (ref "W") (pin "P2") (pinfunction "P$2_P2") (pintype "bidirectional"))
    )
    (net (code "100") (name "unconnected-(W-P$3-PadP3)") (class "Default")
      (node (ref "W") (pin "P3") (pinfunction "P$3_P3") (pintype "bidirectional"))
    )
    (net (code "101") (name "unconnected-(W-P$8-PadP8)") (class "Default")
      (node (ref "W") (pin "P8") (pinfunction "P$8_P8") (pintype "bidirectional"))
    )
    (net (code "102") (name "unconnected-(W-P$9-PadP9)") (class "Default")
      (node (ref "W") (pin "P9") (pinfunction "P$9_P9") (pintype "bidirectional"))
    )
    (net (code "103") (name "unconnected-(W-P$12-PadP12)") (class "Default")
      (node (ref "W") (pin "P12") (pinfunction "P$12_P12") (pintype "bidirectional"))
    )
    (net (code "104") (name "unconnected-(W-P$13-PadP13)") (class "Default")
      (node (ref "W") (pin "P13") (pinfunction "P$13_P13") (pintype "bidirectional"))
    )
    (net (code "105") (name "unconnected-(W-P$18-PadP18)") (class "Default")
      (node (ref "W") (pin "P18") (pinfunction "P$18_P18") (pintype "bidirectional"))
    )
    (net (code "106") (name "unconnected-(W-P$19-PadP19)") (class "Default")
      (node (ref "W") (pin "P19") (pinfunction "P$19_P19") (pintype "bidirectional"))
    )
  )
)
